# SW6208_A_A_B_C_L_MCU_LED.net
KiCad netlist of a schematic drawn in Altium Designer
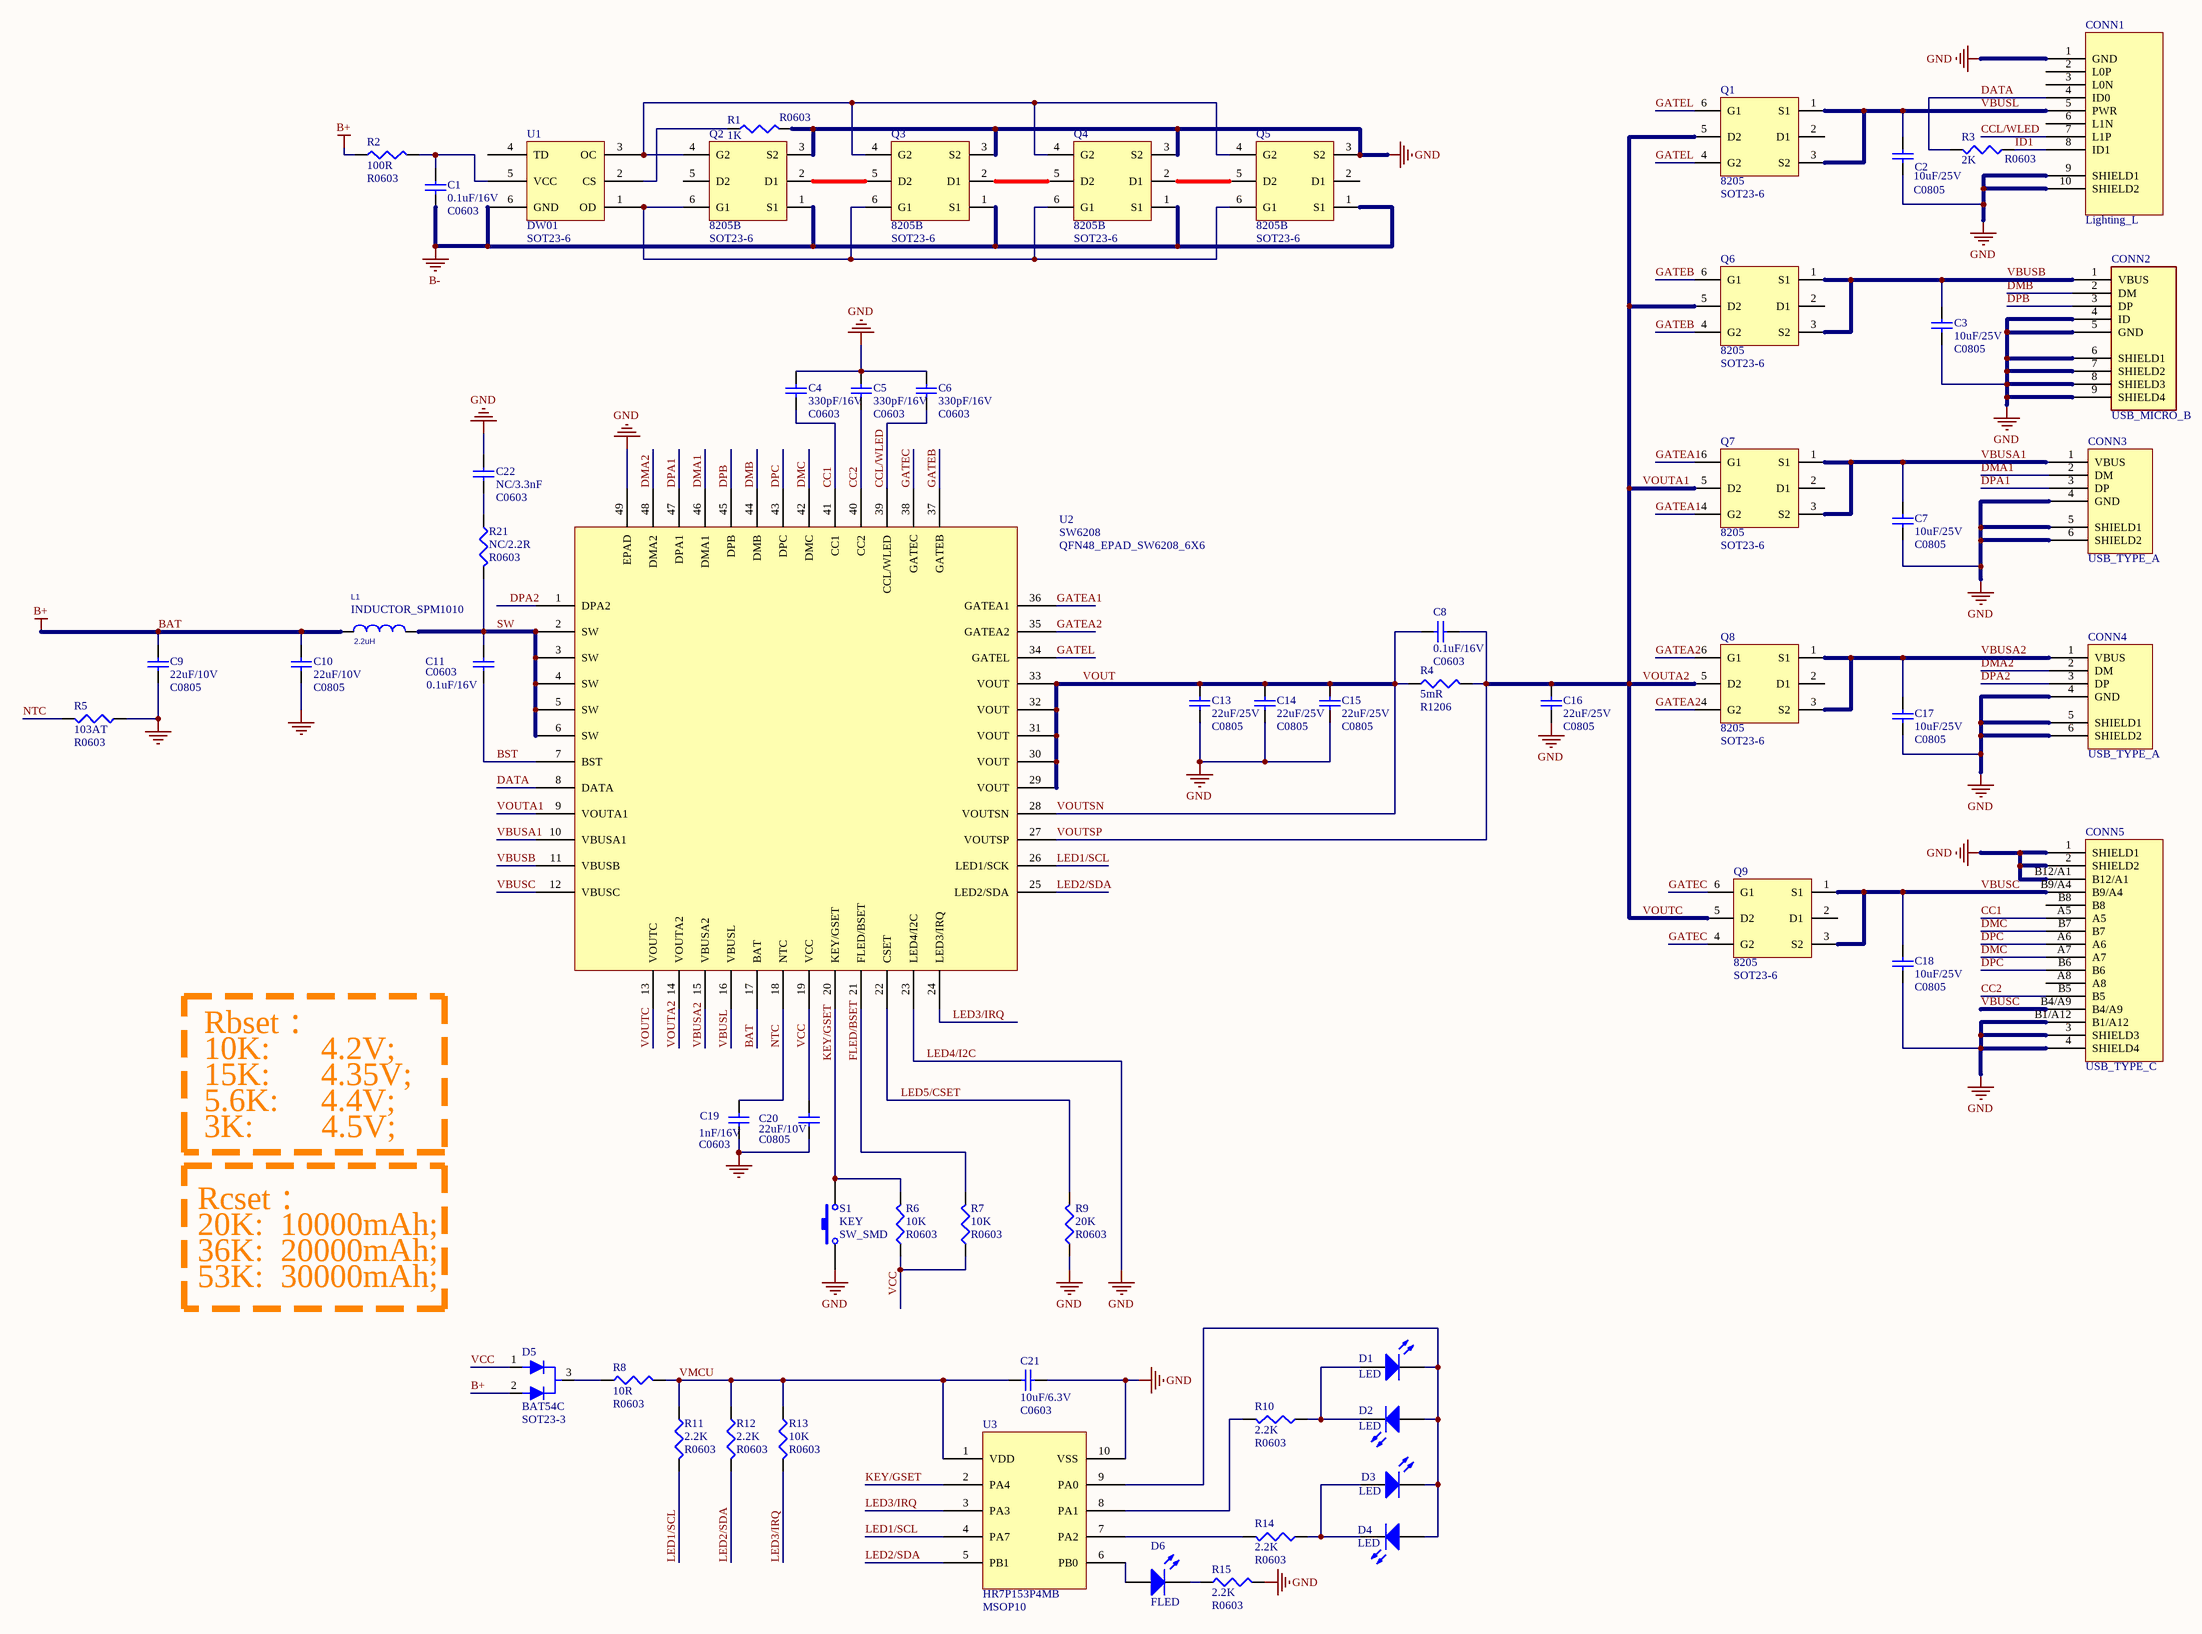
[diagram p0: SW6208+A+A+B+C+L+MCU+LED.SchDoc]

(export (version "E")
  (design (tool "Eeschema 10.0.6"))
  (components
    (comp (ref "C1")
      (value "0.1uF/16V")
      (footprint "C0603")
      (description "Capacitor")
      (fields (field (name "PUBLISHER") "Altium Limited"))
      (libsource (lib "参考设计器件原理图更新") (part "CAP0603"))
    )
    (comp (ref "C2")
      (value "10uF/25V")
      (footprint "C0805")
      (description "Capacitor")
      (fields (field (name "PUBLISHER") "Altium Limited"))
      (libsource (lib "参考设计器件原理图更新") (part "CAP0805"))
    )
    (comp (ref "C3")
      (value "10uF/25V")
      (footprint "C0805")
      (description "Capacitor")
      (fields (field (name "PUBLISHER") "Altium Limited"))
      (libsource (lib "参考设计器件原理图更新") (part "CAP0805"))
    )
    (comp (ref "C4")
      (value "330pF/16V")
      (footprint "C0603")
      (description "Capacitor")
      (fields (field (name "PUBLISHER") "Altium Limited"))
      (libsource (lib "参考设计器件原理图更新") (part "CAP0603"))
    )
    (comp (ref "C5")
      (value "330pF/16V")
      (footprint "C0603")
      (description "Capacitor")
      (fields (field (name "PUBLISHER") "Altium Limited"))
      (libsource (lib "参考设计器件原理图更新") (part "CAP0603"))
    )
    (comp (ref "C6")
      (value "330pF/16V")
      (footprint "C0603")
      (description "Capacitor")
      (fields (field (name "PUBLISHER") "Altium Limited"))
      (libsource (lib "参考设计器件原理图更新") (part "CAP0603"))
    )
    (comp (ref "C7")
      (value "10uF/25V")
      (footprint "C0805")
      (description "Capacitor")
      (fields (field (name "PUBLISHER") "Altium Limited"))
      (libsource (lib "参考设计器件原理图更新") (part "CAP0805"))
    )
    (comp (ref "C8")
      (value "0.1uF/16V")
      (footprint "C0603")
      (description "Capacitor")
      (fields (field (name "PUBLISHER") "Altium Limited"))
      (libsource (lib "参考设计器件原理图更新") (part "CAP0603"))
    )
    (comp (ref "C9")
      (value "22uF/10V")
      (footprint "C0805")
      (description "Capacitor")
      (fields (field (name "PUBLISHER") "Altium Limited"))
      (libsource (lib "参考设计器件原理图更新") (part "CAP0805"))
    )
    (comp (ref "C10")
      (value "22uF/10V")
      (footprint "C0805")
      (description "Capacitor")
      (fields (field (name "PUBLISHER") "Altium Limited"))
      (libsource (lib "参考设计器件原理图更新") (part "CAP0805"))
    )
    (comp (ref "C11")
      (value "0.1uF/16V")
      (footprint "C0603")
      (description "Capacitor")
      (fields (field (name "PUBLISHER") "Altium Limited"))
      (libsource (lib "参考设计器件原理图更新") (part "CAP0603"))
    )
    (comp (ref "C13")
      (value "22uF/25V")
      (footprint "C0805")
      (description "Capacitor")
      (fields (field (name "PUBLISHER") "Altium Limited"))
      (libsource (lib "参考设计器件原理图更新") (part "CAP0805"))
    )
    (comp (ref "C14")
      (value "22uF/25V")
      (footprint "C0805")
      (description "Capacitor")
      (fields (field (name "PUBLISHER") "Altium Limited"))
      (libsource (lib "参考设计器件原理图更新") (part "CAP0805"))
    )
    (comp (ref "C15")
      (value "22uF/25V")
      (footprint "C0805")
      (description "Capacitor")
      (fields (field (name "PUBLISHER") "Altium Limited"))
      (libsource (lib "参考设计器件原理图更新") (part "CAP0805"))
    )
    (comp (ref "C16")
      (value "22uF/25V")
      (footprint "C0805")
      (description "Capacitor")
      (fields (field (name "PUBLISHER") "Altium Limited"))
      (libsource (lib "参考设计器件原理图更新") (part "CAP0805"))
    )
    (comp (ref "C17")
      (value "10uF/25V")
      (footprint "C0805")
      (description "Capacitor")
      (fields (field (name "PUBLISHER") "Altium Limited"))
      (libsource (lib "参考设计器件原理图更新") (part "CAP0805"))
    )
    (comp (ref "C18")
      (value "10uF/25V")
      (footprint "C0805")
      (description "Capacitor")
      (fields (field (name "PUBLISHER") "Altium Limited"))
      (libsource (lib "参考设计器件原理图更新") (part "CAP0805"))
    )
    (comp (ref "C19")
      (value "1nF/16V")
      (footprint "C0603")
      (description "Capacitor")
      (fields (field (name "PUBLISHER") "Altium Limited"))
      (libsource (lib "参考设计器件原理图更新") (part "CAP0603"))
    )
    (comp (ref "C20")
      (value "22uF/10V")
      (footprint "C0805")
      (description "Capacitor")
      (fields (field (name "PUBLISHER") "Altium Limited"))
      (libsource (lib "参考设计器件原理图更新") (part "CAP0805"))
    )
    (comp (ref "C21")
      (value "10uF/6.3V")
      (footprint "C0603")
      (description "Capacitor")
      (fields (field (name "PUBLISHER") "Altium Limited"))
      (libsource (lib "参考设计器件原理图更新") (part "CAP0603"))
    )
    (comp (ref "C22")
      (value "NC/3.3nF")
      (footprint "C0603")
      (description "Capacitor")
      (fields (field (name "PUBLISHER") "Altium Limited"))
      (libsource (lib "参考设计器件原理图更新") (part "CAP0603"))
    )
    (comp (ref "CONN1")
      (value "Lighting_L")
      (footprint "Lighting")
      (libsource (lib "参考设计器件原理图更新") (part "LIGHTING_PORT"))
    )
    (comp (ref "CONN2")
      (value "USB_MICRO_B")
      (footprint "USB_MICRO_B")
      (libsource (lib "参考设计器件原理图更新") (part "USB_MICRO_B"))
    )
    (comp (ref "CONN3")
      (value "USB_TYPE_A")
      (footprint "USB_TYPE_A")
      (libsource (lib "参考设计器件原理图更新") (part "USB_TYPE_A"))
    )
    (comp (ref "CONN4")
      (value "USB_TYPE_A")
      (footprint "USB_TYPE_A")
      (libsource (lib "参考设计器件原理图更新") (part "USB_TYPE_A"))
    )
    (comp (ref "CONN5")
      (value "USB_TYPE_C")
      (footprint "LOUISAD:USB_TYPE_C")
      (libsource (lib "参考设计器件原理图更新") (part "USB_TYPE_C"))
    )
    (comp (ref "D1")
      (value "LED")
      (footprint "LED0603")
      (fields (field (name "PUBLISHER") "Altium Limited"))
      (libsource (lib "参考设计器件原理图更新") (part "LED_0603"))
    )
    (comp (ref "D2")
      (value "LED")
      (footprint "LED0603")
      (fields (field (name "PUBLISHER") "Altium Limited"))
      (libsource (lib "参考设计器件原理图更新") (part "LED_0603"))
    )
    (comp (ref "D3")
      (value "LED")
      (footprint "LED0603")
      (fields (field (name "PUBLISHER") "Altium Limited"))
      (libsource (lib "参考设计器件原理图更新") (part "LED_0603"))
    )
    (comp (ref "D4")
      (value "LED")
      (footprint "LED0603")
      (fields (field (name "PUBLISHER") "Altium Limited"))
      (libsource (lib "参考设计器件原理图更新") (part "LED_0603"))
    )
    (comp (ref "D5")
      (value "BAT54C")
      (footprint "SOT23-3")
      (description "Diode")
      (libsource (lib "参考设计器件原理图更新") (part "BAT54C"))
    )
    (comp (ref "D6")
      (value "FLED")
      (footprint "LED0603")
      (description "LED")
      (fields (field (name "PUBLISHER") "Altium Limited"))
      (libsource (lib "参考设计器件原理图更新") (part "LED_0603"))
    )
    (comp (ref "L1")
      (value "2.2uH")
      (footprint "INDUCTOR_SPM1010")
      (description "INDUCTOR")
      (libsource (lib "参考设计器件原理图更新") (part "INDUCTOR_SPM1010"))
    )
    (comp (ref "Q1")
      (value "8205")
      (footprint "SOT23-6")
      (description "NMOS")
      (fields (field (name "FOOTPRINF") "SOT23-6"))
      (libsource (lib "参考设计器件原理图更新") (part "8205"))
    )
    (comp (ref "Q2")
      (value "8205B")
      (footprint "SOT23-6")
      (description "NMOS")
      (fields (field (name "FOOTPRINF") "SOT23-6"))
      (libsource (lib "") (part "8205_1"))
    )
    (comp (ref "Q3")
      (value "8205B")
      (footprint "SOT23-6")
      (description "NMOS")
      (fields (field (name "FOOTPRINF") "SOT23-6"))
      (libsource (lib "") (part "8205_1"))
    )
    (comp (ref "Q4")
      (value "8205B")
      (footprint "SOT23-6")
      (description "NMOS")
      (fields (field (name "FOOTPRINF") "SOT23-6"))
      (libsource (lib "") (part "8205_1"))
    )
    (comp (ref "Q5")
      (value "8205B")
      (footprint "SOT23-6")
      (description "NMOS")
      (fields (field (name "FOOTPRINF") "SOT23-6"))
      (libsource (lib "") (part "8205_1"))
    )
    (comp (ref "Q6")
      (value "8205")
      (footprint "SOT23-6")
      (description "NMOS")
      (fields (field (name "FOOTPRINF") "SOT23-6"))
      (libsource (lib "参考设计器件原理图更新") (part "8205"))
    )
    (comp (ref "Q7")
      (value "8205")
      (footprint "SOT23-6")
      (description "NMOS")
      (fields (field (name "FOOTPRINF") "SOT23-6"))
      (libsource (lib "参考设计器件原理图更新") (part "8205"))
    )
    (comp (ref "Q8")
      (value "8205")
      (footprint "SOT23-6")
      (description "NMOS")
      (fields (field (name "FOOTPRINF") "SOT23-6"))
      (libsource (lib "参考设计器件原理图更新") (part "8205"))
    )
    (comp (ref "Q9")
      (value "8205")
      (footprint "SOT23-6")
      (description "NMOS")
      (fields (field (name "FOOTPRINF") "SOT23-6"))
      (libsource (lib "参考设计器件原理图更新") (part "8205"))
    )
    (comp (ref "R1")
      (value "1K")
      (footprint "R0603")
      (description "Resistor")
      (fields (field (name "PUBLISHER") "Altium Limited"))
      (libsource (lib "参考设计器件原理图更新") (part "RES_0603"))
    )
    (comp (ref "R2")
      (value "100R")
      (footprint "R0603")
      (description "Resistor")
      (fields (field (name "PUBLISHER") "Altium Limited"))
      (libsource (lib "参考设计器件原理图更新") (part "RES_0603"))
    )
    (comp (ref "R3")
      (value "2K")
      (footprint "R0603")
      (description "Resistor")
      (fields (field (name "PUBLISHER") "Altium Limited"))
      (libsource (lib "参考设计器件原理图更新") (part "RES_0603"))
    )
    (comp (ref "R4")
      (value "5mR")
      (footprint "R1206")
      (description "Resistor")
      (fields (field (name "PUBLISHER") "Altium Limited"))
      (libsource (lib "参考设计器件原理图更新") (part "RES_1206"))
    )
    (comp (ref "R5")
      (value "103AT")
      (footprint "R0603")
      (description "Resistor")
      (fields (field (name "PUBLISHER") "Altium Limited"))
      (libsource (lib "参考设计器件原理图更新") (part "RES_0603"))
    )
    (comp (ref "R6")
      (value "10K")
      (footprint "R0603")
      (description "Resistor")
      (fields (field (name "PUBLISHER") "Altium Limited"))
      (libsource (lib "参考设计器件原理图更新") (part "RES_0603"))
    )
    (comp (ref "R7")
      (value "10K")
      (footprint "R0603")
      (description "Resistor")
      (fields (field (name "PUBLISHER") "Altium Limited"))
      (libsource (lib "参考设计器件原理图更新") (part "RES_0603"))
    )
    (comp (ref "R8")
      (value "10R")
      (footprint "R0603")
      (description "Resistor")
      (fields (field (name "PUBLISHER") "Altium Limited"))
      (libsource (lib "参考设计器件原理图更新") (part "RES_0603"))
    )
    (comp (ref "R9")
      (value "20K")
      (footprint "R0603")
      (description "Resistor")
      (fields (field (name "PUBLISHER") "Altium Limited"))
      (libsource (lib "参考设计器件原理图更新") (part "RES_0603"))
    )
    (comp (ref "R10")
      (value "2.2K")
      (footprint "R0603")
      (description "Resistor")
      (fields (field (name "PUBLISHER") "Altium Limited"))
      (libsource (lib "参考设计器件原理图更新") (part "RES_0603"))
    )
    (comp (ref "R11")
      (value "2.2K")
      (footprint "R0603")
      (description "Resistor")
      (fields (field (name "PUBLISHER") "Altium Limited"))
      (libsource (lib "参考设计器件原理图更新") (part "RES_0603"))
    )
    (comp (ref "R12")
      (value "2.2K")
      (footprint "R0603")
      (description "Resistor")
      (fields (field (name "PUBLISHER") "Altium Limited"))
      (libsource (lib "参考设计器件原理图更新") (part "RES_0603"))
    )
    (comp (ref "R13")
      (value "10K")
      (footprint "R0603")
      (description "Resistor")
      (fields (field (name "PUBLISHER") "Altium Limited"))
      (libsource (lib "参考设计器件原理图更新") (part "RES_0603"))
    )
    (comp (ref "R14")
      (value "2.2K")
      (footprint "R0603")
      (description "Resistor")
      (fields (field (name "PUBLISHER") "Altium Limited"))
      (libsource (lib "参考设计器件原理图更新") (part "RES_0603"))
    )
    (comp (ref "R15")
      (value "2.2K")
      (footprint "R0603")
      (description "Resistor")
      (fields (field (name "PUBLISHER") "Altium Limited"))
      (libsource (lib "参考设计器件原理图更新") (part "RES_0603"))
    )
    (comp (ref "R21")
      (value "NC/2.2R")
      (footprint "R0603")
      (description "Resistor")
      (fields (field (name "PUBLISHER") "Altium Limited"))
      (libsource (lib "参考设计器件原理图更新") (part "RES_0603"))
    )
    (comp (ref "S1")
      (value "KEY")
      (footprint "SW_SMD")
      (fields (field (name "FOOTPRINF") "SW_SMD"))
      (libsource (lib "参考设计器件原理图更新") (part "SW K"))
    )
    (comp (ref "U1")
      (value "DW01")
      (footprint "SOT23-6")
      (description "BAT_PROTECT_IC")
      (libsource (lib "参考设计器件原理图更新") (part "DW01"))
    )
    (comp (ref "U2")
      (value "SW6208")
      (footprint "QFN48_EPAD_SW6208_6X6")
      (description "IC")
      (libsource (lib "芯片型号原理图") (part "SW6208"))
    )
    (comp (ref "U3")
      (value "HR7P153P4MB")
      (footprint "MSOP10")
      (description "MCU")
      (libsource (lib "参考设计器件原理图更新") (part "MCU_MSOP10"))
    )
  )
  (nets
    (net (code "1") (name "/BST") (class "Default")
      (node (ref "C11") (pin "1") (pinfunction "1_1") (pintype "passive"))
      (node (ref "U2") (pin "7") (pinfunction "BST_7") (pintype "passive"))
    )
    (net (code "2") (name "/CC1") (class "Default")
      (node (ref "C4") (pin "1") (pinfunction "1_1") (pintype "passive"))
      (node (ref "CONN5") (pin "A5") (pinfunction "A5_A5") (pintype "passive"))
      (node (ref "U2") (pin "41") (pinfunction "CC1_41") (pintype "passive"))
    )
    (net (code "3") (name "/CC2") (class "Default")
      (node (ref "C5") (pin "1") (pinfunction "1_1") (pintype "passive"))
      (node (ref "CONN5") (pin "B5") (pinfunction "B5_B5") (pintype "passive"))
      (node (ref "U2") (pin "40") (pinfunction "CC2_40") (pintype "passive"))
    )
    (net (code "4") (name "/CCL{slash}WLED") (class "Default")
      (node (ref "C6") (pin "1") (pinfunction "1_1") (pintype "passive"))
      (node (ref "CONN1") (pin "7") (pinfunction "L1P_7") (pintype "passive"))
      (node (ref "U2") (pin "39") (pinfunction "CCL/WLED_39") (pintype "passive"))
    )
    (net (code "5") (name "/DATA") (class "Default")
      (node (ref "CONN1") (pin "4") (pinfunction "ID0_4") (pintype "passive"))
      (node (ref "R3") (pin "2") (pinfunction "2_2") (pintype "passive"))
      (node (ref "U2") (pin "8") (pinfunction "DATA_8") (pintype "passive"))
    )
    (net (code "6") (name "/DMA1") (class "Default")
      (node (ref "CONN3") (pin "2") (pinfunction "DM_2") (pintype "passive"))
      (node (ref "U2") (pin "46") (pinfunction "DMA1_46") (pintype "passive"))
    )
    (net (code "7") (name "/DMA2") (class "Default")
      (node (ref "CONN4") (pin "2") (pinfunction "DM_2") (pintype "passive"))
      (node (ref "U2") (pin "48") (pinfunction "DMA2_48") (pintype "passive"))
    )
    (net (code "8") (name "/DMB") (class "Default")
      (node (ref "CONN2") (pin "2") (pinfunction "DM_2") (pintype "passive"))
      (node (ref "U2") (pin "44") (pinfunction "DMB_44") (pintype "passive"))
    )
    (net (code "9") (name "/DMC") (class "Default")
      (node (ref "CONN5") (pin "A7") (pinfunction "A7_A7") (pintype "passive"))
      (node (ref "CONN5") (pin "B7") (pinfunction "B7_B7") (pintype "passive"))
      (node (ref "U2") (pin "42") (pinfunction "DMC_42") (pintype "passive"))
    )
    (net (code "10") (name "/DPA1") (class "Default")
      (node (ref "CONN3") (pin "3") (pinfunction "DP_3") (pintype "passive"))
      (node (ref "U2") (pin "47") (pinfunction "DPA1_47") (pintype "passive"))
    )
    (net (code "11") (name "/DPA2") (class "Default")
      (node (ref "CONN4") (pin "3") (pinfunction "DP_3") (pintype "passive"))
      (node (ref "U2") (pin "1") (pinfunction "DPA2_1") (pintype "passive"))
    )
    (net (code "12") (name "/DPB") (class "Default")
      (node (ref "CONN2") (pin "3") (pinfunction "DP_3") (pintype "passive"))
      (node (ref "U2") (pin "45") (pinfunction "DPB_45") (pintype "passive"))
    )
    (net (code "13") (name "/DPC") (class "Default")
      (node (ref "CONN5") (pin "A6") (pinfunction "A6_A6") (pintype "passive"))
      (node (ref "CONN5") (pin "B6") (pinfunction "B6_B6") (pintype "passive"))
      (node (ref "U2") (pin "43") (pinfunction "DPC_43") (pintype "passive"))
    )
    (net (code "14") (name "/FLED{slash}BSET") (class "Default")
      (node (ref "R7") (pin "2") (pinfunction "2_2") (pintype "passive"))
      (node (ref "U2") (pin "21") (pinfunction "FLED/BSET_21") (pintype "passive"))
    )
    (net (code "15") (name "/GATEA1") (class "Default")
      (node (ref "Q7") (pin "4") (pinfunction "G2_4") (pintype "passive"))
      (node (ref "Q7") (pin "6") (pinfunction "G1_6") (pintype "passive"))
      (node (ref "U2") (pin "36") (pinfunction "GATEA1_36") (pintype "passive"))
    )
    (net (code "16") (name "/GATEA2") (class "Default")
      (node (ref "Q8") (pin "4") (pinfunction "G2_4") (pintype "passive"))
      (node (ref "Q8") (pin "6") (pinfunction "G1_6") (pintype "passive"))
      (node (ref "U2") (pin "35") (pinfunction "GATEA2_35") (pintype "passive"))
    )
    (net (code "17") (name "/GATEB") (class "Default")
      (node (ref "Q6") (pin "4") (pinfunction "G2_4") (pintype "passive"))
      (node (ref "Q6") (pin "6") (pinfunction "G1_6") (pintype "passive"))
      (node (ref "U2") (pin "37") (pinfunction "GATEB_37") (pintype "passive"))
    )
    (net (code "18") (name "/GATEC") (class "Default")
      (node (ref "Q9") (pin "4") (pinfunction "G2_4") (pintype "passive"))
      (node (ref "Q9") (pin "6") (pinfunction "G1_6") (pintype "passive"))
      (node (ref "U2") (pin "38") (pinfunction "GATEC_38") (pintype "passive"))
    )
    (net (code "19") (name "/GATEL") (class "Default")
      (node (ref "Q1") (pin "4") (pinfunction "G2_4") (pintype "passive"))
      (node (ref "Q1") (pin "6") (pinfunction "G1_6") (pintype "passive"))
      (node (ref "U2") (pin "34") (pinfunction "GATEL_34") (pintype "passive"))
    )
    (net (code "20") (name "/ID1") (class "Default")
      (node (ref "CONN1") (pin "8") (pinfunction "ID1_8") (pintype "passive"))
      (node (ref "R3") (pin "1") (pinfunction "1_1") (pintype "passive"))
    )
    (net (code "21") (name "/KEY{slash}GSET") (class "Default")
      (node (ref "R6") (pin "2") (pinfunction "2_2") (pintype "passive"))
      (node (ref "S1") (pin "2") (pinfunction "2_2") (pintype "passive"))
      (node (ref "U2") (pin "20") (pinfunction "KEY/GSET_20") (pintype "passive"))
      (node (ref "U3") (pin "2") (pinfunction "PA4_2") (pintype "passive"))
    )
    (net (code "22") (name "/LED1{slash}SCL") (class "Default")
      (node (ref "R11") (pin "2") (pinfunction "2_2") (pintype "passive"))
      (node (ref "U2") (pin "26") (pinfunction "LED1/SCK_26") (pintype "passive"))
      (node (ref "U3") (pin "4") (pinfunction "PA7_4") (pintype "passive"))
    )
    (net (code "23") (name "/LED2{slash}SDA") (class "Default")
      (node (ref "R12") (pin "2") (pinfunction "2_2") (pintype "passive"))
      (node (ref "U2") (pin "25") (pinfunction "LED2/SDA_25") (pintype "passive"))
      (node (ref "U3") (pin "5") (pinfunction "PB1_5") (pintype "passive"))
    )
    (net (code "24") (name "/LED3{slash}IRQ") (class "Default")
      (node (ref "R13") (pin "2") (pinfunction "2_2") (pintype "passive"))
      (node (ref "U2") (pin "24") (pinfunction "LED3/IRQ_24") (pintype "passive"))
      (node (ref "U3") (pin "3") (pinfunction "PA3_3") (pintype "passive"))
    )
    (net (code "25") (name "/LED5{slash}CSET") (class "Default")
      (node (ref "R9") (pin "2") (pinfunction "2_2") (pintype "passive"))
      (node (ref "U2") (pin "22") (pinfunction "CSET_22") (pintype "passive"))
    )
    (net (code "26") (name "/NTC") (class "Default")
      (node (ref "C19") (pin "1") (pinfunction "1_1") (pintype "passive"))
      (node (ref "R5") (pin "2") (pinfunction "2_2") (pintype "passive"))
      (node (ref "U2") (pin "18") (pinfunction "NTC_18") (pintype "passive"))
    )
    (net (code "27") (name "/SW") (class "Default")
      (node (ref "C11") (pin "2") (pinfunction "2_2") (pintype "passive"))
      (node (ref "L1") (pin "2") (pinfunction "2_2") (pintype "passive"))
      (node (ref "R21") (pin "2") (pinfunction "2_2") (pintype "passive"))
      (node (ref "U2") (pin "2") (pinfunction "SW_2") (pintype "passive"))
      (node (ref "U2") (pin "3") (pinfunction "SW_3") (pintype "passive"))
      (node (ref "U2") (pin "4") (pinfunction "SW_4") (pintype "passive"))
      (node (ref "U2") (pin "5") (pinfunction "SW_5") (pintype "passive"))
      (node (ref "U2") (pin "6") (pinfunction "SW_6") (pintype "passive"))
    )
    (net (code "28") (name "/VBUSA1") (class "Default")
      (node (ref "C7") (pin "2") (pinfunction "2_2") (pintype "passive"))
      (node (ref "CONN3") (pin "1") (pinfunction "VBUS_1") (pintype "passive"))
      (node (ref "Q7") (pin "1") (pinfunction "S1_1") (pintype "passive"))
      (node (ref "Q7") (pin "3") (pinfunction "S2_3") (pintype "passive"))
      (node (ref "U2") (pin "10") (pinfunction "VBUSA1_10") (pintype "passive"))
    )
    (net (code "29") (name "/VBUSA2") (class "Default")
      (node (ref "C17") (pin "2") (pinfunction "2_2") (pintype "passive"))
      (node (ref "CONN4") (pin "1") (pinfunction "VBUS_1") (pintype "passive"))
      (node (ref "Q8") (pin "1") (pinfunction "S1_1") (pintype "passive"))
      (node (ref "Q8") (pin "3") (pinfunction "S2_3") (pintype "passive"))
      (node (ref "U2") (pin "15") (pinfunction "VBUSA2_15") (pintype "passive"))
    )
    (net (code "30") (name "/VBUSB") (class "Default")
      (node (ref "C3") (pin "2") (pinfunction "2_2") (pintype "passive"))
      (node (ref "CONN2") (pin "1") (pinfunction "VBUS_1") (pintype "passive"))
      (node (ref "Q6") (pin "1") (pinfunction "S1_1") (pintype "passive"))
      (node (ref "Q6") (pin "3") (pinfunction "S2_3") (pintype "passive"))
      (node (ref "U2") (pin "11") (pinfunction "VBUSB_11") (pintype "passive"))
    )
    (net (code "31") (name "/VBUSC") (class "Default")
      (node (ref "C18") (pin "2") (pinfunction "2_2") (pintype "passive"))
      (node (ref "CONN5") (pin "B4/A9") (pinfunction "B4/A9_B4/A9") (pintype "passive"))
      (node (ref "CONN5") (pin "B9/A4") (pinfunction "B9/A4_B9/A4") (pintype "passive"))
      (node (ref "Q9") (pin "1") (pinfunction "S1_1") (pintype "passive"))
      (node (ref "Q9") (pin "3") (pinfunction "S2_3") (pintype "passive"))
      (node (ref "U2") (pin "12") (pinfunction "VBUSC_12") (pintype "passive"))
    )
    (net (code "32") (name "/VBUSL") (class "Default")
      (node (ref "C2") (pin "2") (pinfunction "2_2") (pintype "passive"))
      (node (ref "CONN1") (pin "5") (pinfunction "PWR_5") (pintype "passive"))
      (node (ref "Q1") (pin "1") (pinfunction "S1_1") (pintype "passive"))
      (node (ref "Q1") (pin "3") (pinfunction "S2_3") (pintype "passive"))
      (node (ref "U2") (pin "16") (pinfunction "VBUSL_16") (pintype "passive"))
    )
    (net (code "33") (name "/VCC") (class "Default")
      (node (ref "C20") (pin "1") (pinfunction "1_1") (pintype "passive"))
      (node (ref "D5") (pin "1") (pintype "passive"))
      (node (ref "R6") (pin "1") (pinfunction "1_1") (pintype "passive"))
      (node (ref "R7") (pin "1") (pinfunction "1_1") (pintype "passive"))
      (node (ref "U2") (pin "19") (pinfunction "VCC_19") (pintype "passive"))
    )
    (net (code "34") (name "/VMCU") (class "Default")
      (node (ref "C21") (pin "1") (pinfunction "1_1") (pintype "passive"))
      (node (ref "R11") (pin "1") (pinfunction "1_1") (pintype "passive"))
      (node (ref "R12") (pin "1") (pinfunction "1_1") (pintype "passive"))
      (node (ref "R13") (pin "1") (pinfunction "1_1") (pintype "passive"))
      (node (ref "R8") (pin "2") (pinfunction "2_2") (pintype "passive"))
      (node (ref "U3") (pin "1") (pinfunction "VDD_1") (pintype "passive"))
    )
    (net (code "35") (name "/VOUT") (class "Default")
      (node (ref "C13") (pin "2") (pinfunction "2_2") (pintype "passive"))
      (node (ref "C14") (pin "2") (pinfunction "2_2") (pintype "passive"))
      (node (ref "C15") (pin "2") (pinfunction "2_2") (pintype "passive"))
      (node (ref "C8") (pin "1") (pinfunction "1_1") (pintype "passive"))
      (node (ref "R4") (pin "1") (pinfunction "1_1") (pintype "passive"))
      (node (ref "U2") (pin "28") (pinfunction "VOUTSN_28") (pintype "passive"))
      (node (ref "U2") (pin "29") (pinfunction "VOUT_29") (pintype "passive"))
      (node (ref "U2") (pin "30") (pinfunction "VOUT_30") (pintype "passive"))
      (node (ref "U2") (pin "31") (pinfunction "VOUT_31") (pintype "passive"))
      (node (ref "U2") (pin "32") (pinfunction "VOUT_32") (pintype "passive"))
      (node (ref "U2") (pin "33") (pinfunction "VOUT_33") (pintype "passive"))
    )
    (net (code "36") (name "/VOUTA1") (class "Default")
      (node (ref "C16") (pin "2") (pinfunction "2_2") (pintype "passive"))
      (node (ref "C8") (pin "2") (pinfunction "2_2") (pintype "passive"))
      (node (ref "Q1") (pin "5") (pinfunction "D2_5") (pintype "passive"))
      (node (ref "Q6") (pin "5") (pinfunction "D2_5") (pintype "passive"))
      (node (ref "Q7") (pin "5") (pinfunction "D2_5") (pintype "passive"))
      (node (ref "Q8") (pin "5") (pinfunction "D2_5") (pintype "passive"))
      (node (ref "Q9") (pin "5") (pinfunction "D2_5") (pintype "passive"))
      (node (ref "R4") (pin "2") (pinfunction "2_2") (pintype "passive"))
      (node (ref "U2") (pin "13") (pinfunction "VOUTC_13") (pintype "passive"))
      (node (ref "U2") (pin "14") (pinfunction "VOUTA2_14") (pintype "passive"))
      (node (ref "U2") (pin "27") (pinfunction "VOUTSP_27") (pintype "passive"))
      (node (ref "U2") (pin "9") (pinfunction "VOUTA1_9") (pintype "passive"))
    )
    (net (code "37") (name "B+") (class "Default")
      (node (ref "C10") (pin "2") (pinfunction "2_2") (pintype "passive"))
      (node (ref "C9") (pin "2") (pinfunction "2_2") (pintype "passive"))
      (node (ref "D5") (pin "2") (pintype "passive"))
      (node (ref "L1") (pin "1") (pinfunction "1_1") (pintype "passive"))
      (node (ref "R2") (pin "1") (pinfunction "1_1") (pintype "passive"))
      (node (ref "U2") (pin "17") (pinfunction "BAT_17") (pintype "passive"))
    )
    (net (code "38") (name "B-") (class "Default")
      (node (ref "C1") (pin "1") (pinfunction "1_1") (pintype "passive"))
      (node (ref "Q2") (pin "1") (pinfunction "S1_1") (pintype "passive"))
      (node (ref "Q3") (pin "1") (pinfunction "S1_1") (pintype "passive"))
      (node (ref "Q4") (pin "1") (pinfunction "S1_1") (pintype "passive"))
      (node (ref "Q5") (pin "1") (pinfunction "S1_1") (pintype "passive"))
      (node (ref "U1") (pin "6") (pinfunction "GND_6") (pintype "passive"))
    )
    (net (code "39") (name "GND") (class "Default")
      (node (ref "C10") (pin "1") (pinfunction "1_1") (pintype "passive"))
      (node (ref "C13") (pin "1") (pinfunction "1_1") (pintype "passive"))
      (node (ref "C14") (pin "1") (pinfunction "1_1") (pintype "passive"))
      (node (ref "C15") (pin "1") (pinfunction "1_1") (pintype "passive"))
      (node (ref "C16") (pin "1") (pinfunction "1_1") (pintype "passive"))
      (node (ref "C17") (pin "1") (pinfunction "1_1") (pintype "passive"))
      (node (ref "C18") (pin "1") (pinfunction "1_1") (pintype "passive"))
      (node (ref "C19") (pin "2") (pinfunction "2_2") (pintype "passive"))
      (node (ref "C2") (pin "1") (pinfunction "1_1") (pintype "passive"))
      (node (ref "C20") (pin "2") (pinfunction "2_2") (pintype "passive"))
      (node (ref "C21") (pin "2") (pinfunction "2_2") (pintype "passive"))
      (node (ref "C22") (pin "2") (pinfunction "2_2") (pintype "passive"))
      (node (ref "C3") (pin "1") (pinfunction "1_1") (pintype "passive"))
      (node (ref "C4") (pin "2") (pinfunction "2_2") (pintype "passive"))
      (node (ref "C5") (pin "2") (pinfunction "2_2") (pintype "passive"))
      (node (ref "C6") (pin "2") (pinfunction "2_2") (pintype "passive"))
      (node (ref "C7") (pin "1") (pinfunction "1_1") (pintype "passive"))
      (node (ref "C9") (pin "1") (pinfunction "1_1") (pintype "passive"))
      (node (ref "CONN1") (pin "1") (pinfunction "GND_1") (pintype "passive"))
      (node (ref "CONN1") (pin "10") (pinfunction "SHIELD2_10") (pintype "passive"))
      (node (ref "CONN1") (pin "9") (pinfunction "SHIELD1_9") (pintype "passive"))
      (node (ref "CONN2") (pin "4") (pinfunction "ID_4") (pintype "passive"))
      (node (ref "CONN2") (pin "5") (pinfunction "GND_5") (pintype "passive"))
      (node (ref "CONN2") (pin "6") (pinfunction "SHIELD1_6") (pintype "passive"))
      (node (ref "CONN2") (pin "7") (pinfunction "SHIELD2_7") (pintype "passive"))
      (node (ref "CONN2") (pin "8") (pinfunction "SHIELD3_8") (pintype "passive"))
      (node (ref "CONN2") (pin "9") (pinfunction "SHIELD4_9") (pintype "passive"))
      (node (ref "CONN3") (pin "4") (pinfunction "GND_4") (pintype "passive"))
      (node (ref "CONN3") (pin "5") (pinfunction "SHIELD1_5") (pintype "passive"))
      (node (ref "CONN3") (pin "6") (pinfunction "SHIELD2_6") (pintype "passive"))
      (node (ref "CONN4") (pin "4") (pinfunction "GND_4") (pintype "passive"))
      (node (ref "CONN4") (pin "5") (pinfunction "SHIELD1_5") (pintype "passive"))
      (node (ref "CONN4") (pin "6") (pinfunction "SHIELD2_6") (pintype "passive"))
      (node (ref "CONN5") (pin "1") (pinfunction "SHIELD1_1") (pintype "passive"))
      (node (ref "CONN5") (pin "2") (pinfunction "SHIELD2_2") (pintype "passive"))
      (node (ref "CONN5") (pin "3") (pinfunction "SHIELD3_3") (pintype "passive"))
      (node (ref "CONN5") (pin "4") (pinfunction "SHIELD4_4") (pintype "passive"))
      (node (ref "CONN5") (pin "B1/A12") (pinfunction "B1/A12_B1/A12") (pintype "passive"))
      (node (ref "CONN5") (pin "B12/A1") (pinfunction "B12/A1_B12/A1") (pintype "passive"))
      (node (ref "Q2") (pin "3") (pinfunction "S2_3") (pintype "passive"))
      (node (ref "Q3") (pin "3") (pinfunction "S2_3") (pintype "passive"))
      (node (ref "Q4") (pin "3") (pinfunction "S2_3") (pintype "passive"))
      (node (ref "Q5") (pin "3") (pinfunction "S2_3") (pintype "passive"))
      (node (ref "R1") (pin "2") (pinfunction "2_2") (pintype "passive"))
      (node (ref "R15") (pin "2") (pinfunction "2_2") (pintype "passive"))
      (node (ref "R5") (pin "1") (pinfunction "1_1") (pintype "passive"))
      (node (ref "R9") (pin "1") (pinfunction "1_1") (pintype "passive"))
      (node (ref "S1") (pin "1") (pinfunction "1_1") (pintype "passive"))
      (node (ref "U2") (pin "23") (pinfunction "LED4/I2C_23") (pintype "passive"))
      (node (ref "U2") (pin "49") (pinfunction "EPAD_49") (pintype "passive"))
      (node (ref "U3") (pin "10") (pinfunction "VSS_10") (pintype "passive"))
    )
    (net (code "40") (name "Net-(C22-Pad1)") (class "Default")
      (node (ref "C22") (pin "1") (pinfunction "1_1") (pintype "passive"))
      (node (ref "R21") (pin "1") (pinfunction "1_1") (pintype "passive"))
    )
    (net (code "41") (name "Net-(D1-A)") (class "Default")
      (node (ref "D1") (pin "1") (pinfunction "A_1") (pintype "passive"))
      (node (ref "D2") (pin "2") (pinfunction "K_2") (pintype "passive"))
      (node (ref "R10") (pin "1") (pinfunction "1_1") (pintype "passive"))
    )
    (net (code "42") (name "Net-(D1-K)") (class "Default")
      (node (ref "D1") (pin "2") (pinfunction "K_2") (pintype "passive"))
      (node (ref "D2") (pin "1") (pinfunction "A_1") (pintype "passive"))
      (node (ref "D3") (pin "2") (pinfunction "K_2") (pintype "passive"))
      (node (ref "D4") (pin "1") (pinfunction "A_1") (pintype "passive"))
      (node (ref "U3") (pin "9") (pinfunction "PA0_9") (pintype "passive"))
    )
    (net (code "43") (name "Net-(D3-A)") (class "Default")
      (node (ref "D3") (pin "1") (pinfunction "A_1") (pintype "passive"))
      (node (ref "D4") (pin "2") (pinfunction "K_2") (pintype "passive"))
      (node (ref "R14") (pin "1") (pinfunction "1_1") (pintype "passive"))
    )
    (net (code "44") (name "Net-(D5-Pad3)") (class "Default")
      (node (ref "D5") (pin "3") (pintype "passive"))
      (node (ref "R8") (pin "1") (pinfunction "1_1") (pintype "passive"))
    )
    (net (code "45") (name "Net-(D6-A)") (class "Default")
      (node (ref "D6") (pin "1") (pinfunction "A_1") (pintype "passive"))
      (node (ref "U3") (pin "6") (pinfunction "PB0_6") (pintype "passive"))
    )
    (net (code "46") (name "Net-(D6-K)") (class "Default")
      (node (ref "D6") (pin "2") (pinfunction "K_2") (pintype "passive"))
      (node (ref "R15") (pin "1") (pinfunction "1_1") (pintype "passive"))
    )
    (net (code "47") (name "Net-(Q2-D1)") (class "Default")
      (node (ref "Q2") (pin "2") (pinfunction "D1_2") (pintype "passive"))
      (node (ref "Q3") (pin "5") (pinfunction "D2_5") (pintype "passive"))
    )
    (net (code "48") (name "Net-(Q2-G1)") (class "Default")
      (node (ref "Q2") (pin "6") (pinfunction "G1_6") (pintype "passive"))
      (node (ref "Q3") (pin "6") (pinfunction "G1_6") (pintype "passive"))
      (node (ref "Q4") (pin "6") (pinfunction "G1_6") (pintype "passive"))
      (node (ref "Q5") (pin "6") (pinfunction "G1_6") (pintype "passive"))
      (node (ref "U1") (pin "1") (pinfunction "OD_1") (pintype "passive"))
    )
    (net (code "49") (name "Net-(Q2-G2)") (class "Default")
      (node (ref "Q2") (pin "4") (pinfunction "G2_4") (pintype "passive"))
      (node (ref "Q3") (pin "4") (pinfunction "G2_4") (pintype "passive"))
      (node (ref "Q4") (pin "4") (pinfunction "G2_4") (pintype "passive"))
      (node (ref "Q5") (pin "4") (pinfunction "G2_4") (pintype "passive"))
      (node (ref "U1") (pin "3") (pinfunction "OC_3") (pintype "passive"))
    )
    (net (code "50") (name "Net-(Q3-D1)") (class "Default")
      (node (ref "Q3") (pin "2") (pinfunction "D1_2") (pintype "passive"))
      (node (ref "Q4") (pin "5") (pinfunction "D2_5") (pintype "passive"))
    )
    (net (code "51") (name "Net-(Q4-D1)") (class "Default")
      (node (ref "Q4") (pin "2") (pinfunction "D1_2") (pintype "passive"))
      (node (ref "Q5") (pin "5") (pinfunction "D2_5") (pintype "passive"))
    )
    (net (code "52") (name "Net-(U1-CS)") (class "Default")
      (node (ref "R1") (pin "1") (pinfunction "1_1") (pintype "passive"))
      (node (ref "U1") (pin "2") (pinfunction "CS_2") (pintype "passive"))
    )
    (net (code "53") (name "Net-(U1-VCC)") (class "Default")
      (node (ref "C1") (pin "2") (pinfunction "2_2") (pintype "passive"))
      (node (ref "R2") (pin "2") (pinfunction "2_2") (pintype "passive"))
      (node (ref "U1") (pin "5") (pinfunction "VCC_5") (pintype "passive"))
    )
    (net (code "54") (name "Net-(U3-PA1)") (class "Default")
      (node (ref "R10") (pin "2") (pinfunction "2_2") (pintype "passive"))
      (node (ref "U3") (pin "8") (pinfunction "PA1_8") (pintype "passive"))
    )
    (net (code "55") (name "Net-(U3-PA2)") (class "Default")
      (node (ref "R14") (pin "2") (pinfunction "2_2") (pintype "passive"))
      (node (ref "U3") (pin "7") (pinfunction "PA2_7") (pintype "passive"))
    )
    (net (code "56") (name "unconnected-(CONN1-L0N-Pad3)") (class "Default")
      (node (ref "CONN1") (pin "3") (pinfunction "L0N_3") (pintype "passive"))
    )
    (net (code "57") (name "unconnected-(CONN1-L0P-Pad2)") (class "Default")
      (node (ref "CONN1") (pin "2") (pinfunction "L0P_2") (pintype "passive"))
    )
    (net (code "58") (name "unconnected-(CONN1-L1N-Pad6)") (class "Default")
      (node (ref "CONN1") (pin "6") (pinfunction "L1N_6") (pintype "passive"))
    )
    (net (code "59") (name "unconnected-(CONN5-PadA8)") (class "Default")
      (node (ref "CONN5") (pin "A8") (pinfunction "A8_A8") (pintype "passive"))
    )
    (net (code "60") (name "unconnected-(CONN5-PadB8)") (class "Default")
      (node (ref "CONN5") (pin "B8") (pinfunction "B8_B8") (pintype "passive"))
    )
    (net (code "61") (name "unconnected-(Q1-D1-Pad2)") (class "Default")
      (node (ref "Q1") (pin "2") (pinfunction "D1_2") (pintype "passive"))
    )
    (net (code "62") (name "unconnected-(Q2-D2-Pad5)") (class "Default")
      (node (ref "Q2") (pin "5") (pinfunction "D2_5") (pintype "passive"))
    )
    (net (code "63") (name "unconnected-(Q5-D1-Pad2)") (class "Default")
      (node (ref "Q5") (pin "2") (pinfunction "D1_2") (pintype "passive"))
    )
    (net (code "64") (name "unconnected-(Q6-D1-Pad2)") (class "Default")
      (node (ref "Q6") (pin "2") (pinfunction "D1_2") (pintype "passive"))
    )
    (net (code "65") (name "unconnected-(Q7-D1-Pad2)") (class "Default")
      (node (ref "Q7") (pin "2") (pinfunction "D1_2") (pintype "passive"))
    )
    (net (code "66") (name "unconnected-(Q8-D1-Pad2)") (class "Default")
      (node (ref "Q8") (pin "2") (pinfunction "D1_2") (pintype "passive"))
    )
    (net (code "67") (name "unconnected-(Q9-D1-Pad2)") (class "Default")
      (node (ref "Q9") (pin "2") (pinfunction "D1_2") (pintype "passive"))
    )
    (net (code "68") (name "unconnected-(U1-TD-Pad4)") (class "Default")
      (node (ref "U1") (pin "4") (pinfunction "TD_4") (pintype "passive"))
    )
  )
)
